# XBEE.net
KiCad netlist of a schematic drawn in EAGLE
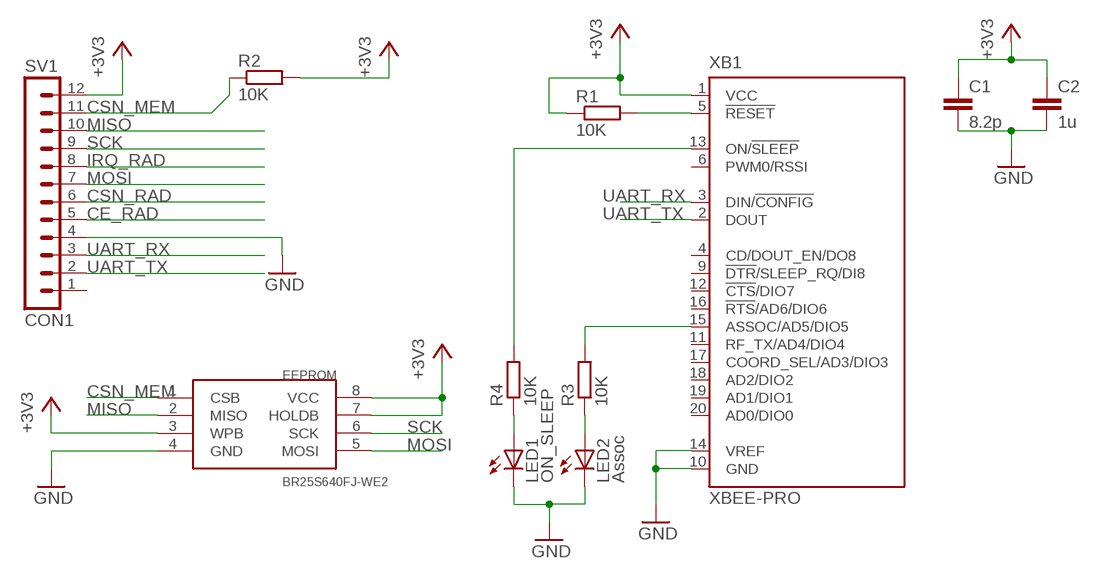
[diagram p0: schematic, sheet 1]

(export (version "E")
  (design (tool "Eeschema 10.0.6"))
  (components
    (comp (ref "C1")
      (value "8.2p")
      (footprint "eagle-import:C1206")
      (libsource (lib "eagle-import") (part "C-EUC1206"))
    )
    (comp (ref "C2")
      (value "1u")
      (footprint "eagle-import:C1206")
      (libsource (lib "eagle-import") (part "C-EUC1206"))
    )
    (comp (ref "EEPROM")
      (value "BR25S640FJ-WE2")
      (footprint "eagle-import:SO8")
      (libsource (lib "eagle-import") (part "BR25S640FJ-WE2"))
    )
    (comp (ref "LED1")
      (value "ON_SLEEP")
      (footprint "eagle-import:1206")
      (libsource (lib "eagle-import") (part "LEDSMT1206"))
    )
    (comp (ref "LED2")
      (value "Assoc")
      (footprint "eagle-import:1206")
      (libsource (lib "eagle-import") (part "LEDSMT1206"))
    )
    (comp (ref "R1")
      (value "10K")
      (footprint "eagle-import:R1206")
      (libsource (lib "eagle-import") (part "R-EU_R1206"))
    )
    (comp (ref "R2")
      (value "10K")
      (footprint "eagle-import:R1206")
      (libsource (lib "eagle-import") (part "R-EU_R1206"))
    )
    (comp (ref "R3")
      (value "10K")
      (footprint "eagle-import:R1206")
      (libsource (lib "eagle-import") (part "R-EU_R1206"))
    )
    (comp (ref "R4")
      (value "10K")
      (footprint "eagle-import:R1206")
      (libsource (lib "eagle-import") (part "R-EU_R1206"))
    )
    (comp (ref "SV1")
      (value "CON1")
      (footprint "eagle-import:MA12-1W")
      (libsource (lib "eagle-import") (part "MA12-1W"))
    )
    (comp (ref "XB1")
      (value "XBEE-PRO")
      (footprint "eagle-import:XBEE-PRO")
      (fields (field (name "MPN") "XBP24-AWI-001"))
      (libsource (lib "eagle-import") (part "XBEE-PRO"))
    )
  )
  (nets
    (net (code "1") (name "+3V3") (class "Default")
      (node (ref "C1") (pin "1") (pinfunction "1_1") (pintype "passive"))
      (node (ref "C2") (pin "1") (pinfunction "1_1") (pintype "passive"))
      (node (ref "EEPROM") (pin "3") (pinfunction "WPB_3") (pintype "bidirectional"))
      (node (ref "EEPROM") (pin "7") (pinfunction "HOLDB_7") (pintype "bidirectional"))
      (node (ref "EEPROM") (pin "8") (pinfunction "VCC_8") (pintype "bidirectional"))
      (node (ref "R1") (pin "1") (pinfunction "1_1") (pintype "passive"))
      (node (ref "R2") (pin "2") (pinfunction "2_2") (pintype "passive"))
      (node (ref "SV1") (pin "12") (pinfunction "12_12") (pintype "passive"))
      (node (ref "XB1") (pin "1") (pinfunction "VCC_1") (pintype "power_in"))
    )
    (net (code "2") (name "/CE_RAD") (class "Default")
      (node (ref "SV1") (pin "5") (pinfunction "5_5") (pintype "passive"))
    )
    (net (code "3") (name "/CSN_MEM") (class "Default")
      (node (ref "EEPROM") (pin "1") (pinfunction "CSB_1") (pintype "bidirectional"))
      (node (ref "R2") (pin "1") (pinfunction "1_1") (pintype "passive"))
      (node (ref "SV1") (pin "11") (pinfunction "11_11") (pintype "passive"))
    )
    (net (code "4") (name "/CSN_RAD") (class "Default")
      (node (ref "SV1") (pin "6") (pinfunction "6_6") (pintype "passive"))
    )
    (net (code "5") (name "/IRQ_RAD") (class "Default")
      (node (ref "SV1") (pin "8") (pinfunction "8_8") (pintype "passive"))
    )
    (net (code "6") (name "/MISO") (class "Default")
      (node (ref "EEPROM") (pin "2") (pinfunction "MISO_2") (pintype "bidirectional"))
      (node (ref "SV1") (pin "10") (pinfunction "10_10") (pintype "passive"))
    )
    (net (code "7") (name "/MOSI") (class "Default")
      (node (ref "EEPROM") (pin "5") (pinfunction "MOSI_5") (pintype "bidirectional"))
      (node (ref "SV1") (pin "7") (pinfunction "7_7") (pintype "passive"))
    )
    (net (code "8") (name "/SCK") (class "Default")
      (node (ref "EEPROM") (pin "6") (pinfunction "SCK_6") (pintype "bidirectional"))
      (node (ref "SV1") (pin "9") (pinfunction "9_9") (pintype "passive"))
    )
    (net (code "9") (name "/UART_RX") (class "Default")
      (node (ref "SV1") (pin "3") (pinfunction "3_3") (pintype "passive"))
      (node (ref "XB1") (pin "3") (pinfunction "DIN/~{CONFIG}_3") (pintype "input"))
    )
    (net (code "10") (name "/UART_TX") (class "Default")
      (node (ref "SV1") (pin "2") (pinfunction "2_2") (pintype "passive"))
      (node (ref "XB1") (pin "2") (pinfunction "DOUT_2") (pintype "output"))
    )
    (net (code "11") (name "GND") (class "Default")
      (node (ref "C1") (pin "2") (pinfunction "2_2") (pintype "passive"))
      (node (ref "C2") (pin "2") (pinfunction "2_2") (pintype "passive"))
      (node (ref "EEPROM") (pin "4") (pinfunction "GND_4") (pintype "bidirectional"))
      (node (ref "LED1") (pin "C") (pinfunction "C_C") (pintype "passive"))
      (node (ref "LED2") (pin "C") (pinfunction "C_C") (pintype "passive"))
      (node (ref "SV1") (pin "4") (pinfunction "4_4") (pintype "passive"))
      (node (ref "XB1") (pin "10") (pinfunction "GND_10") (pintype "power_in"))
      (node (ref "XB1") (pin "14") (pinfunction "VREF_14") (pintype "input"))
    )
    (net (code "12") (name "Net-(LED1-PadA)") (class "Default")
      (node (ref "LED1") (pin "A") (pinfunction "A_A") (pintype "passive"))
      (node (ref "R4") (pin "1") (pinfunction "1_1") (pintype "passive"))
    )
    (net (code "13") (name "Net-(LED2-PadA)") (class "Default")
      (node (ref "LED2") (pin "A") (pinfunction "A_A") (pintype "passive"))
      (node (ref "R3") (pin "1") (pinfunction "1_1") (pintype "passive"))
    )
    (net (code "14") (name "Net-(XB1-ASSOC{slash}AD5{slash}DIO5)") (class "Default")
      (node (ref "R3") (pin "2") (pinfunction "2_2") (pintype "passive"))
      (node (ref "XB1") (pin "15") (pinfunction "ASSOC/AD5/DIO5_15") (pintype "bidirectional"))
    )
    (net (code "15") (name "Net-(XB1-ON{slash}~{SLEEP})") (class "Default")
      (node (ref "R4") (pin "2") (pinfunction "2_2") (pintype "passive"))
      (node (ref "XB1") (pin "13") (pinfunction "ON/~{SLEEP}_13") (pintype "output"))
    )
    (net (code "16") (name "Net-(XB1-~{RESET})") (class "Default")
      (node (ref "R1") (pin "2") (pinfunction "2_2") (pintype "passive"))
      (node (ref "XB1") (pin "5") (pinfunction "~{RESET}_5") (pintype "input"))
    )
    (net (code "17") (name "unconnected-(SV1-Pad1)") (class "Default")
      (node (ref "SV1") (pin "1") (pinfunction "1_1") (pintype "passive"))
    )
    (net (code "18") (name "unconnected-(XB1-AD0{slash}DIO0-Pad20)") (class "Default")
      (node (ref "XB1") (pin "20") (pinfunction "AD0/DIO0_20") (pintype "bidirectional"))
    )
    (net (code "19") (name "unconnected-(XB1-AD1{slash}DIO1-Pad19)") (class "Default")
      (node (ref "XB1") (pin "19") (pinfunction "AD1/DIO1_19") (pintype "bidirectional"))
    )
    (net (code "20") (name "unconnected-(XB1-AD2{slash}DIO2-Pad18)") (class "Default")
      (node (ref "XB1") (pin "18") (pinfunction "AD2/DIO2_18") (pintype "bidirectional"))
    )
    (net (code "21") (name "unconnected-(XB1-CD{slash}DOUT_EN{slash}DO8-Pad4)") (class "Default")
      (node (ref "XB1") (pin "4") (pinfunction "CD/DOUT_EN/DO8_4") (pintype "output"))
    )
    (net (code "22") (name "unconnected-(XB1-COORD_SEL{slash}AD3{slash}DIO3-Pad17)") (class "Default")
      (node (ref "XB1") (pin "17") (pinfunction "COORD_SEL/AD3/DIO3_17") (pintype "bidirectional"))
    )
    (net (code "23") (name "unconnected-(XB1-PWM0{slash}RSSI-Pad6)") (class "Default")
      (node (ref "XB1") (pin "6") (pinfunction "PWM0/RSSI_6") (pintype "output"))
    )
    (net (code "24") (name "unconnected-(XB1-RF_TX{slash}AD4{slash}DIO4-Pad11)") (class "Default")
      (node (ref "XB1") (pin "11") (pinfunction "RF_TX/AD4/DIO4_11") (pintype "bidirectional"))
    )
    (net (code "25") (name "unconnected-(XB1-~{CTS}{slash}DIO7-Pad12)") (class "Default")
      (node (ref "XB1") (pin "12") (pinfunction "~{CTS}/DIO7_12") (pintype "bidirectional"))
    )
    (net (code "26") (name "unconnected-(XB1-~{DTR}{slash}SLEEP_RQ{slash}DI8-Pad9)") (class "Default")
      (node (ref "XB1") (pin "9") (pinfunction "~{DTR}/SLEEP_RQ/DI8_9") (pintype "bidirectional"))
    )
    (net (code "27") (name "unconnected-(XB1-~{RTS}{slash}AD6{slash}DIO6-Pad16)") (class "Default")
      (node (ref "XB1") (pin "16") (pinfunction "~{RTS}/AD6/DIO6_16") (pintype "bidirectional"))
    )
  )
)
